# Telephone_Emulator.net
KiCad netlist of a schematic drawn in Altium Designer
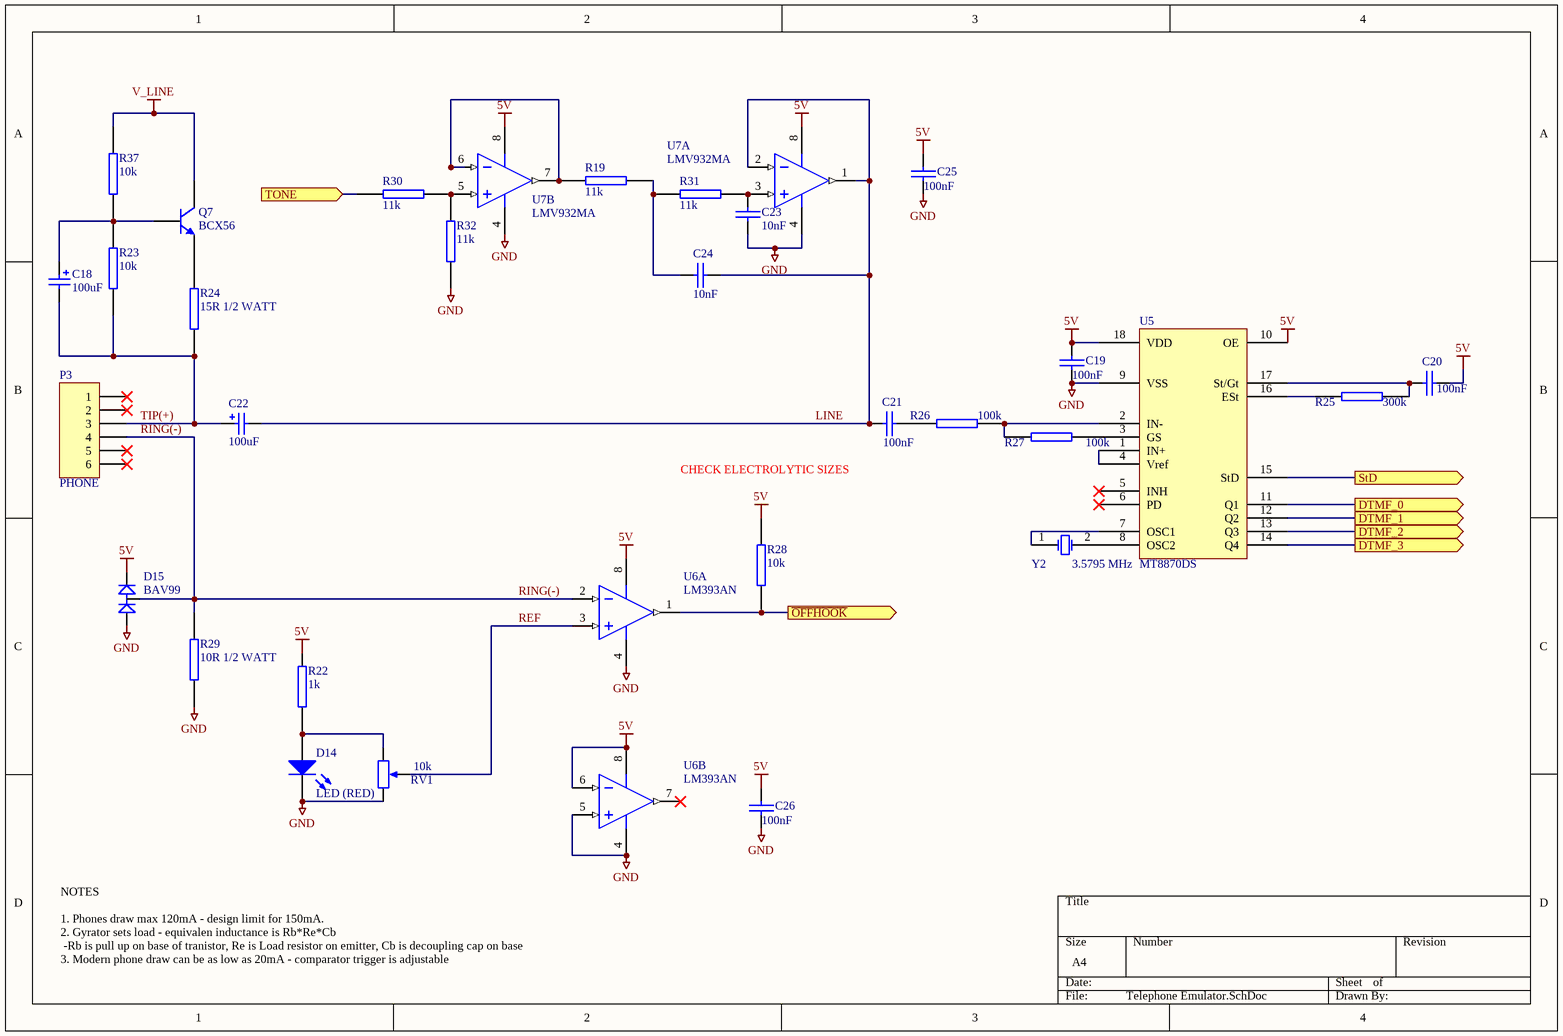
[diagram p0: Telephone Emulator.SchDoc]

(export (version "E")
  (design (tool "Eeschema 10.0.6"))
  (components
    (comp (ref "C18")
      (value "100uF")
      (footprint "CAP ELECTRO SIZE-E")
      (description "100uF 25V")
      (fields
        (field (name "MANUFACTURER") "Cornell Dubilier")
        (field (name "MOUSER PART NO.") "598-AVE107M25E16T-F")
      )
      (libsource (lib "NASCO Electrolytic") (part "100uF 25V ALU E"))
    )
    (comp (ref "C19")
      (value "100nF")
      (footprint "CAP (3D) - 0603")
      (description "CAPACITOR SMD 0402")
      (libsource (lib "401 CCPA") (part "CAP"))
    )
    (comp (ref "C20")
      (value "100nF")
      (footprint "CAP (3D) - 0603")
      (description "CAPACITOR SMD 0402")
      (libsource (lib "401 CCPA") (part "CAP"))
    )
    (comp (ref "C21")
      (value "100nF")
      (footprint "CAP (3D) - 0603")
      (description "CAPACITOR SMD 0402")
      (libsource (lib "401 CCPA") (part "CAP"))
    )
    (comp (ref "C22")
      (value "100uF")
      (footprint "CAP ELECTRO SIZE-E")
      (description "100uF 25V")
      (fields
        (field (name "MANUFACTURER") "Cornell Dubilier")
        (field (name "MOUSER PART NO.") "598-AVE107M25E16T-F")
      )
      (libsource (lib "NASCO Electrolytic") (part "100uF 25V ALU E"))
    )
    (comp (ref "C23")
      (value "10nF")
      (footprint "CAP (3D) - 0603")
      (description "CAPACITOR SMD 0603")
      (libsource (lib "NASCO Capacitors") (part "CAP SMD 0603 100nF"))
    )
    (comp (ref "C24")
      (value "10nF")
      (footprint "CAP (3D) - 0603")
      (description "CAPACITOR SMD 0603")
      (libsource (lib "NASCO Capacitors") (part "CAP SMD 0603 100nF"))
    )
    (comp (ref "C25")
      (value "100nF")
      (footprint "CAP (3D) - 0603")
      (description "CAPACITOR SMD 0402")
      (libsource (lib "401 CCPA") (part "CAP"))
    )
    (comp (ref "C26")
      (value "100nF")
      (footprint "CAP (3D) - 0603")
      (description "CAPACITOR SMD 0402")
      (libsource (lib "401 CCPA") (part "CAP"))
    )
    (comp (ref "D14")
      (value "LED (RED)")
      (footprint "LED(3D) RED - 0805")
      (description "LED 0805 RED")
      (libsource (lib "NASCO") (part "LED 0805 RED"))
    )
    (comp (ref "D15")
      (value "BAV99")
      (footprint "SOT23-3L")
      (description "DUAL DIODE, BAV99")
      (fields (field (name "MOUSER PART NO.") "771-BAV99/T3") (field (name "FARNELL PART NO.") "9843612"))
      (libsource (lib "NASCO") (part "BAV99"))
    )
    (comp (ref "P3")
      (value "PHONE")
      (footprint "MOLEXZ RJ11")
      (description "Header, 6-Pin")
      (fields (field (name "MOUSER PART NO.") "43860-0020"))
      (libsource (lib "Miscellaneous Connectors") (part "Header 6"))
    )
    (comp (ref "Q7")
      (value "BCX56")
      (footprint "SOT89")
      (description "NPN Bipolar Transistor")
      (fields
        (field (name "MANUFACTURER") "NXP Semiconductors")
        (field (name "MOUSER PART NO.") "771-BCX56-16135")
      )
      (libsource (lib "NASCO") (part "BCX56"))
    )
    (comp (ref "R19")
      (value "11k")
      (footprint "RES (3D) - 0603")
      (description "RESISTOR SMD 0603 1k")
      (libsource (lib "NASCO Resistors") (part "RES SMD 0603 1k"))
    )
    (comp (ref "R22")
      (value "1k")
      (footprint "RES (3D) - 0603")
      (description "RESISTOR SMD 0603 1k")
      (fields (field (name "MOUSER PART NO.") "652-CR0603-JW-102ELF") (field (name "MANUFACTURER") "Bourns"))
      (libsource (lib "NASCO Resistors") (part "RES SMD 0603 1k"))
    )
    (comp (ref "R23")
      (value "10k")
      (footprint "RES (3D) - 0603")
      (description "RESISTOR SMD 0603 10k")
      (fields (field (name "MOUSER PART NO.") "652-CR0603FX-1002ELF") (field (name "MANUFACTURER") "Bourns"))
      (libsource (lib "NASCO Resistors") (part "RES SMD 0603 10k"))
    )
    (comp (ref "R24")
      (value "15R 1/2 WATT")
      (footprint "RES (3D) - 1210")
      (description "RESISTOR SMD 0603")
      (fields (field (name "MOUSER PART NO.") "ERJ-14NF15R0U"))
      (libsource (lib "NASCO Resistors") (part "RES SMD 0603 100R"))
    )
    (comp (ref "R25")
      (value "300k")
      (footprint "RES (3D) - 0603")
      (description "RESISTOR SMD 0603")
      (libsource (lib "NASCO Resistors") (part "RES SMD 0603 100R"))
    )
    (comp (ref "R26")
      (value "100k")
      (footprint "RES (3D) - 0603")
      (description "RESISTOR SMD 0603")
      (libsource (lib "NASCO Resistors") (part "RES SMD 0603 100R"))
    )
    (comp (ref "R27")
      (value "100k")
      (footprint "RES (3D) - 0603")
      (description "RESISTOR SMD 0603")
      (libsource (lib "NASCO Resistors") (part "RES SMD 0603 100R"))
    )
    (comp (ref "R28")
      (value "10k")
      (footprint "RES (3D) - 0603")
      (description "RESISTOR SMD 0603")
      (libsource (lib "NASCO Resistors") (part "RES SMD 0603 100R"))
    )
    (comp (ref "R29")
      (value "10R 1/2 WATT")
      (footprint "RES (3D) - 1210")
      (description "RESISTOR SMD 0603")
      (fields (field (name "MOUSER PART NO.") "ERJ-14NF10R0U"))
      (libsource (lib "NASCO Resistors") (part "RES SMD 0603 100R"))
    )
    (comp (ref "R30")
      (value "11k")
      (footprint "RES (3D) - 0603")
      (description "RESISTOR SMD 0603 1k")
      (libsource (lib "NASCO Resistors") (part "RES SMD 0603 1k"))
    )
    (comp (ref "R31")
      (value "11k")
      (footprint "RES (3D) - 0603")
      (description "RESISTOR SMD 0603 1k")
      (libsource (lib "NASCO Resistors") (part "RES SMD 0603 1k"))
    )
    (comp (ref "R32")
      (value "11k")
      (footprint "RES (3D) - 0603")
      (description "RESISTOR SMD 0603 1k")
      (libsource (lib "NASCO Resistors") (part "RES SMD 0603 1k"))
    )
    (comp (ref "R37")
      (value "10k")
      (footprint "RES (3D) - 0603")
      (description "RESISTOR SMD 0603 10k")
      (fields (field (name "MOUSER PART NO.") "652-CR0603FX-1002ELF") (field (name "MANUFACTURER") "Bourns"))
      (libsource (lib "NASCO Resistors") (part "RES SMD 0603 10k"))
    )
    (comp (ref "RV1")
      (value "10k")
      (footprint "TRIMPOT - PVZ3A")
      (description "Variable Resistor")
      (libsource (lib "NASCO") (part "VAR (POT) SMD"))
    )
    (comp (ref "U5")
      (value "MT8870DS")
      (footprint "SOIC-18")
      (description "MT8870 DTMF DECODER")
      (libsource (lib "NASCO") (part "MT8870"))
    )
    (comp (ref "U6")
      (value "LM393AN")
      (footprint "SO-8")
      (description "Dual Comparator")
      (libsource (lib "Motorola Analog Comparator") (part "LM393AN"))
    )
    (comp (ref "U7")
      (value "LMV932MA")
      (footprint "SO-8")
      (description "Low Power Dual Operational Amplifier, 8-pin Narrow SOIC")
      (libsource (lib "SIM900") (part "LMV932MA/NOPB"))
    )
    (comp (ref "Y2")
      (value "3.5795 MHz")
      (footprint "HC49/4H_SMX")
      (description "Crystal Oscillator")
      (libsource (lib "Miscellaneous Devices") (part "XTAL"))
    )
  )
  (nets
    (net (code "1") (name "/DTMF_0") (class "Default")
      (node (ref "U5") (pin "11") (pinfunction "Q1_11") (pintype "passive"))
    )
    (net (code "2") (name "/DTMF_1") (class "Default")
      (node (ref "U5") (pin "12") (pinfunction "Q2_12") (pintype "passive"))
    )
    (net (code "3") (name "/DTMF_2") (class "Default")
      (node (ref "U5") (pin "13") (pinfunction "Q3_13") (pintype "passive"))
    )
    (net (code "4") (name "/DTMF_3") (class "Default")
      (node (ref "U5") (pin "14") (pinfunction "Q4_14") (pintype "passive"))
    )
    (net (code "5") (name "/LINE") (class "Default")
      (node (ref "C21") (pin "2") (pinfunction "2_2") (pintype "passive"))
      (node (ref "C22") (pin "2") (pinfunction "2_2") (pintype "passive"))
      (node (ref "C24") (pin "2") (pinfunction "2_2") (pintype "passive"))
      (node (ref "U7") (pin "1") (pinfunction "OUTA_1") (pintype "output"))
      (node (ref "U7") (pin "2") (pinfunction "INA-_2") (pintype "input"))
    )
    (net (code "6") (name "/REF") (class "Default")
      (node (ref "RV1") (pin "2") (pinfunction "2_2") (pintype "passive"))
      (node (ref "U6") (pin "3") (pinfunction "IN+_3") (pintype "input"))
    )
    (net (code "7") (name "/RING(-)") (class "Default")
      (node (ref "D15") (pin "3") (pinfunction "C1/A2_3") (pintype "passive"))
      (node (ref "P3") (pin "4") (pinfunction "4_4") (pintype "passive"))
      (node (ref "R29") (pin "2") (pinfunction "2_2") (pintype "passive"))
      (node (ref "U6") (pin "2") (pinfunction "IN-_2") (pintype "input"))
    )
    (net (code "8") (name "/StD") (class "Default")
      (node (ref "U5") (pin "15") (pinfunction "StD_15") (pintype "passive"))
    )
    (net (code "9") (name "/TIP(+)") (class "Default")
      (node (ref "C18") (pin "2") (pinfunction "2_2") (pintype "passive"))
      (node (ref "C22") (pin "1") (pinfunction "1_1") (pintype "passive"))
      (node (ref "P3") (pin "3") (pinfunction "3_3") (pintype "passive"))
      (node (ref "R23") (pin "1") (pinfunction "1_1") (pintype "passive"))
      (node (ref "R24") (pin "1") (pinfunction "1_1") (pintype "passive"))
    )
    (net (code "10") (name "/TONE") (class "Default")
      (node (ref "R30") (pin "1") (pinfunction "1_1") (pintype "passive"))
    )
    (net (code "11") (name "/~{OFFHOOK}") (class "Default")
      (node (ref "R28") (pin "1") (pinfunction "1_1") (pintype "passive"))
      (node (ref "U6") (pin "1") (pinfunction "OUT_1") (pintype "output"))
    )
    (net (code "12") (name "5V") (class "Default")
      (node (ref "C19") (pin "1") (pinfunction "1_1") (pintype "passive"))
      (node (ref "C20") (pin "1") (pinfunction "1_1") (pintype "passive"))
      (node (ref "C25") (pin "1") (pinfunction "1_1") (pintype "passive"))
      (node (ref "C26") (pin "1") (pinfunction "1_1") (pintype "passive"))
      (node (ref "D15") (pin "2") (pinfunction "C2_2") (pintype "passive"))
      (node (ref "R28") (pin "2") (pinfunction "2_2") (pintype "passive"))
      (node (ref "U5") (pin "10") (pinfunction "OE_10") (pintype "passive"))
      (node (ref "U5") (pin "18") (pinfunction "VDD_18") (pintype "passive"))
      (node (ref "U6") (pin "6") (pinfunction "IN-_6") (pintype "input"))
      (node (ref "U6") (pin "8") (pinfunction "V+_8") (pintype "power_in"))
      (node (ref "U7") (pin "8") (pinfunction "V+_8") (pintype "power_in"))
    )
    (net (code "13") (name "GND") (class "Default")
      (node (ref "C19") (pin "2") (pinfunction "2_2") (pintype "passive"))
      (node (ref "C23") (pin "2") (pinfunction "2_2") (pintype "passive"))
      (node (ref "C25") (pin "2") (pinfunction "2_2") (pintype "passive"))
      (node (ref "C26") (pin "2") (pinfunction "2_2") (pintype "passive"))
      (node (ref "D14") (pin "2") (pinfunction "K_2") (pintype "passive"))
      (node (ref "D15") (pin "1") (pinfunction "A1_1") (pintype "passive"))
      (node (ref "R29") (pin "1") (pinfunction "1_1") (pintype "passive"))
      (node (ref "R32") (pin "1") (pinfunction "1_1") (pintype "passive"))
      (node (ref "RV1") (pin "3") (pinfunction "3_3") (pintype "passive"))
      (node (ref "U5") (pin "9") (pinfunction "VSS_9") (pintype "passive"))
      (node (ref "U6") (pin "4") (pinfunction "GND_4") (pintype "power_in"))
      (node (ref "U6") (pin "5") (pinfunction "IN+_5") (pintype "input"))
      (node (ref "U7") (pin "4") (pinfunction "GND_4") (pintype "power_in"))
    )
    (net (code "14") (name "Net-(C21-Pad1)") (class "Default")
      (node (ref "C21") (pin "1") (pinfunction "1_1") (pintype "passive"))
      (node (ref "R26") (pin "1") (pinfunction "1_1") (pintype "passive"))
    )
    (net (code "15") (name "Net-(C24-Pad1)") (class "Default")
      (node (ref "C24") (pin "1") (pinfunction "1_1") (pintype "passive"))
      (node (ref "R19") (pin "2") (pinfunction "2_2") (pintype "passive"))
      (node (ref "R31") (pin "1") (pinfunction "1_1") (pintype "passive"))
    )
    (net (code "16") (name "Net-(D14-A)") (class "Default")
      (node (ref "D14") (pin "1") (pinfunction "A_1") (pintype "passive"))
      (node (ref "R22") (pin "1") (pinfunction "1_1") (pintype "passive"))
      (node (ref "RV1") (pin "1") (pinfunction "1_1") (pintype "passive"))
    )
    (net (code "17") (name "Net-(Q7-B)") (class "Default")
      (node (ref "C18") (pin "1") (pinfunction "1_1") (pintype "passive"))
      (node (ref "Q7") (pin "3") (pinfunction "B_3") (pintype "passive"))
      (node (ref "R23") (pin "2") (pinfunction "2_2") (pintype "passive"))
      (node (ref "R37") (pin "1") (pinfunction "1_1") (pintype "passive"))
    )
    (net (code "18") (name "Net-(Q7-E)") (class "Default")
      (node (ref "Q7") (pin "1") (pinfunction "E_1") (pintype "passive"))
      (node (ref "R24") (pin "2") (pinfunction "2_2") (pintype "passive"))
    )
    (net (code "19") (name "Net-(U5-ESt)") (class "Default")
      (node (ref "R25") (pin "1") (pinfunction "1_1") (pintype "passive"))
      (node (ref "U5") (pin "16") (pinfunction "ESt_16") (pintype "passive"))
    )
    (net (code "20") (name "Net-(U5-GS)") (class "Default")
      (node (ref "R27") (pin "2") (pinfunction "2_2") (pintype "passive"))
      (node (ref "U5") (pin "3") (pinfunction "GS_3") (pintype "passive"))
    )
    (net (code "21") (name "Net-(U5-IN+)") (class "Default")
      (node (ref "U5") (pin "1") (pinfunction "IN+_1") (pintype "passive"))
      (node (ref "U5") (pin "4") (pinfunction "Vref_4") (pintype "passive"))
    )
    (net (code "22") (name "Net-(U5-IN-)") (class "Default")
      (node (ref "R26") (pin "2") (pinfunction "2_2") (pintype "passive"))
      (node (ref "R27") (pin "1") (pinfunction "1_1") (pintype "passive"))
      (node (ref "U5") (pin "2") (pinfunction "IN-_2") (pintype "passive"))
    )
    (net (code "23") (name "Net-(U5-OSC1)") (class "Default")
      (node (ref "U5") (pin "7") (pinfunction "OSC1_7") (pintype "passive"))
      (node (ref "Y2") (pin "1") (pinfunction "OSC1_1") (pintype "passive"))
    )
    (net (code "24") (name "Net-(U5-OSC2)") (class "Default")
      (node (ref "U5") (pin "8") (pinfunction "OSC2_8") (pintype "passive"))
      (node (ref "Y2") (pin "2") (pinfunction "OSC2_2") (pintype "passive"))
    )
    (net (code "25") (name "Net-(U5-St{slash}Gt)") (class "Default")
      (node (ref "C20") (pin "2") (pinfunction "2_2") (pintype "passive"))
      (node (ref "R25") (pin "2") (pinfunction "2_2") (pintype "passive"))
      (node (ref "U5") (pin "17") (pinfunction "St/Gt_17") (pintype "passive"))
    )
    (net (code "26") (name "Net-(U7A-INA+)") (class "Default")
      (node (ref "C23") (pin "1") (pinfunction "1_1") (pintype "passive"))
      (node (ref "R31") (pin "2") (pinfunction "2_2") (pintype "passive"))
      (node (ref "U7") (pin "3") (pinfunction "INA+_3") (pintype "input"))
    )
    (net (code "27") (name "Net-(U7B-INB+)") (class "Default")
      (node (ref "R30") (pin "2") (pinfunction "2_2") (pintype "passive"))
      (node (ref "R32") (pin "2") (pinfunction "2_2") (pintype "passive"))
      (node (ref "U7") (pin "5") (pinfunction "INB+_5") (pintype "input"))
    )
    (net (code "28") (name "Net-(U7B-INB-)") (class "Default")
      (node (ref "R19") (pin "1") (pinfunction "1_1") (pintype "passive"))
      (node (ref "U7") (pin "6") (pinfunction "INB-_6") (pintype "input"))
      (node (ref "U7") (pin "7") (pinfunction "OUTB_7") (pintype "output"))
    )
    (net (code "29") (name "V_LINE") (class "Default")
      (node (ref "Q7") (pin "2") (pinfunction "C_2") (pintype "passive"))
      (node (ref "R37") (pin "2") (pinfunction "2_2") (pintype "passive"))
    )
    (net (code "30") (name "unconnected-(P3-Pad1)") (class "Default")
      (node (ref "P3") (pin "1") (pinfunction "1_1") (pintype "passive+no_connect"))
    )
    (net (code "31") (name "unconnected-(P3-Pad2)") (class "Default")
      (node (ref "P3") (pin "2") (pinfunction "2_2") (pintype "passive+no_connect"))
    )
    (net (code "32") (name "unconnected-(P3-Pad5)") (class "Default")
      (node (ref "P3") (pin "5") (pinfunction "5_5") (pintype "passive+no_connect"))
    )
    (net (code "33") (name "unconnected-(P3-Pad6)") (class "Default")
      (node (ref "P3") (pin "6") (pinfunction "6_6") (pintype "passive+no_connect"))
    )
    (net (code "34") (name "unconnected-(R22-Pad2)") (class "Default")
      (node (ref "R22") (pin "2") (pinfunction "2_2") (pintype "passive"))
    )
    (net (code "35") (name "unconnected-(U5-INH-Pad5)") (class "Default")
      (node (ref "U5") (pin "5") (pinfunction "INH_5") (pintype "passive+no_connect"))
    )
    (net (code "36") (name "unconnected-(U5-PD-Pad6)") (class "Default")
      (node (ref "U5") (pin "6") (pinfunction "PD_6") (pintype "passive+no_connect"))
    )
    (net (code "37") (name "unconnected-(U6B-OUT-Pad7)") (class "Default")
      (node (ref "U6") (pin "7") (pinfunction "OUT_7") (pintype "output+no_connect"))
    )
  )
)
